# ReuseBlock_OPA847_2025-08-02.net
KiCad netlist of a schematic drawn in EasyEDA Pro
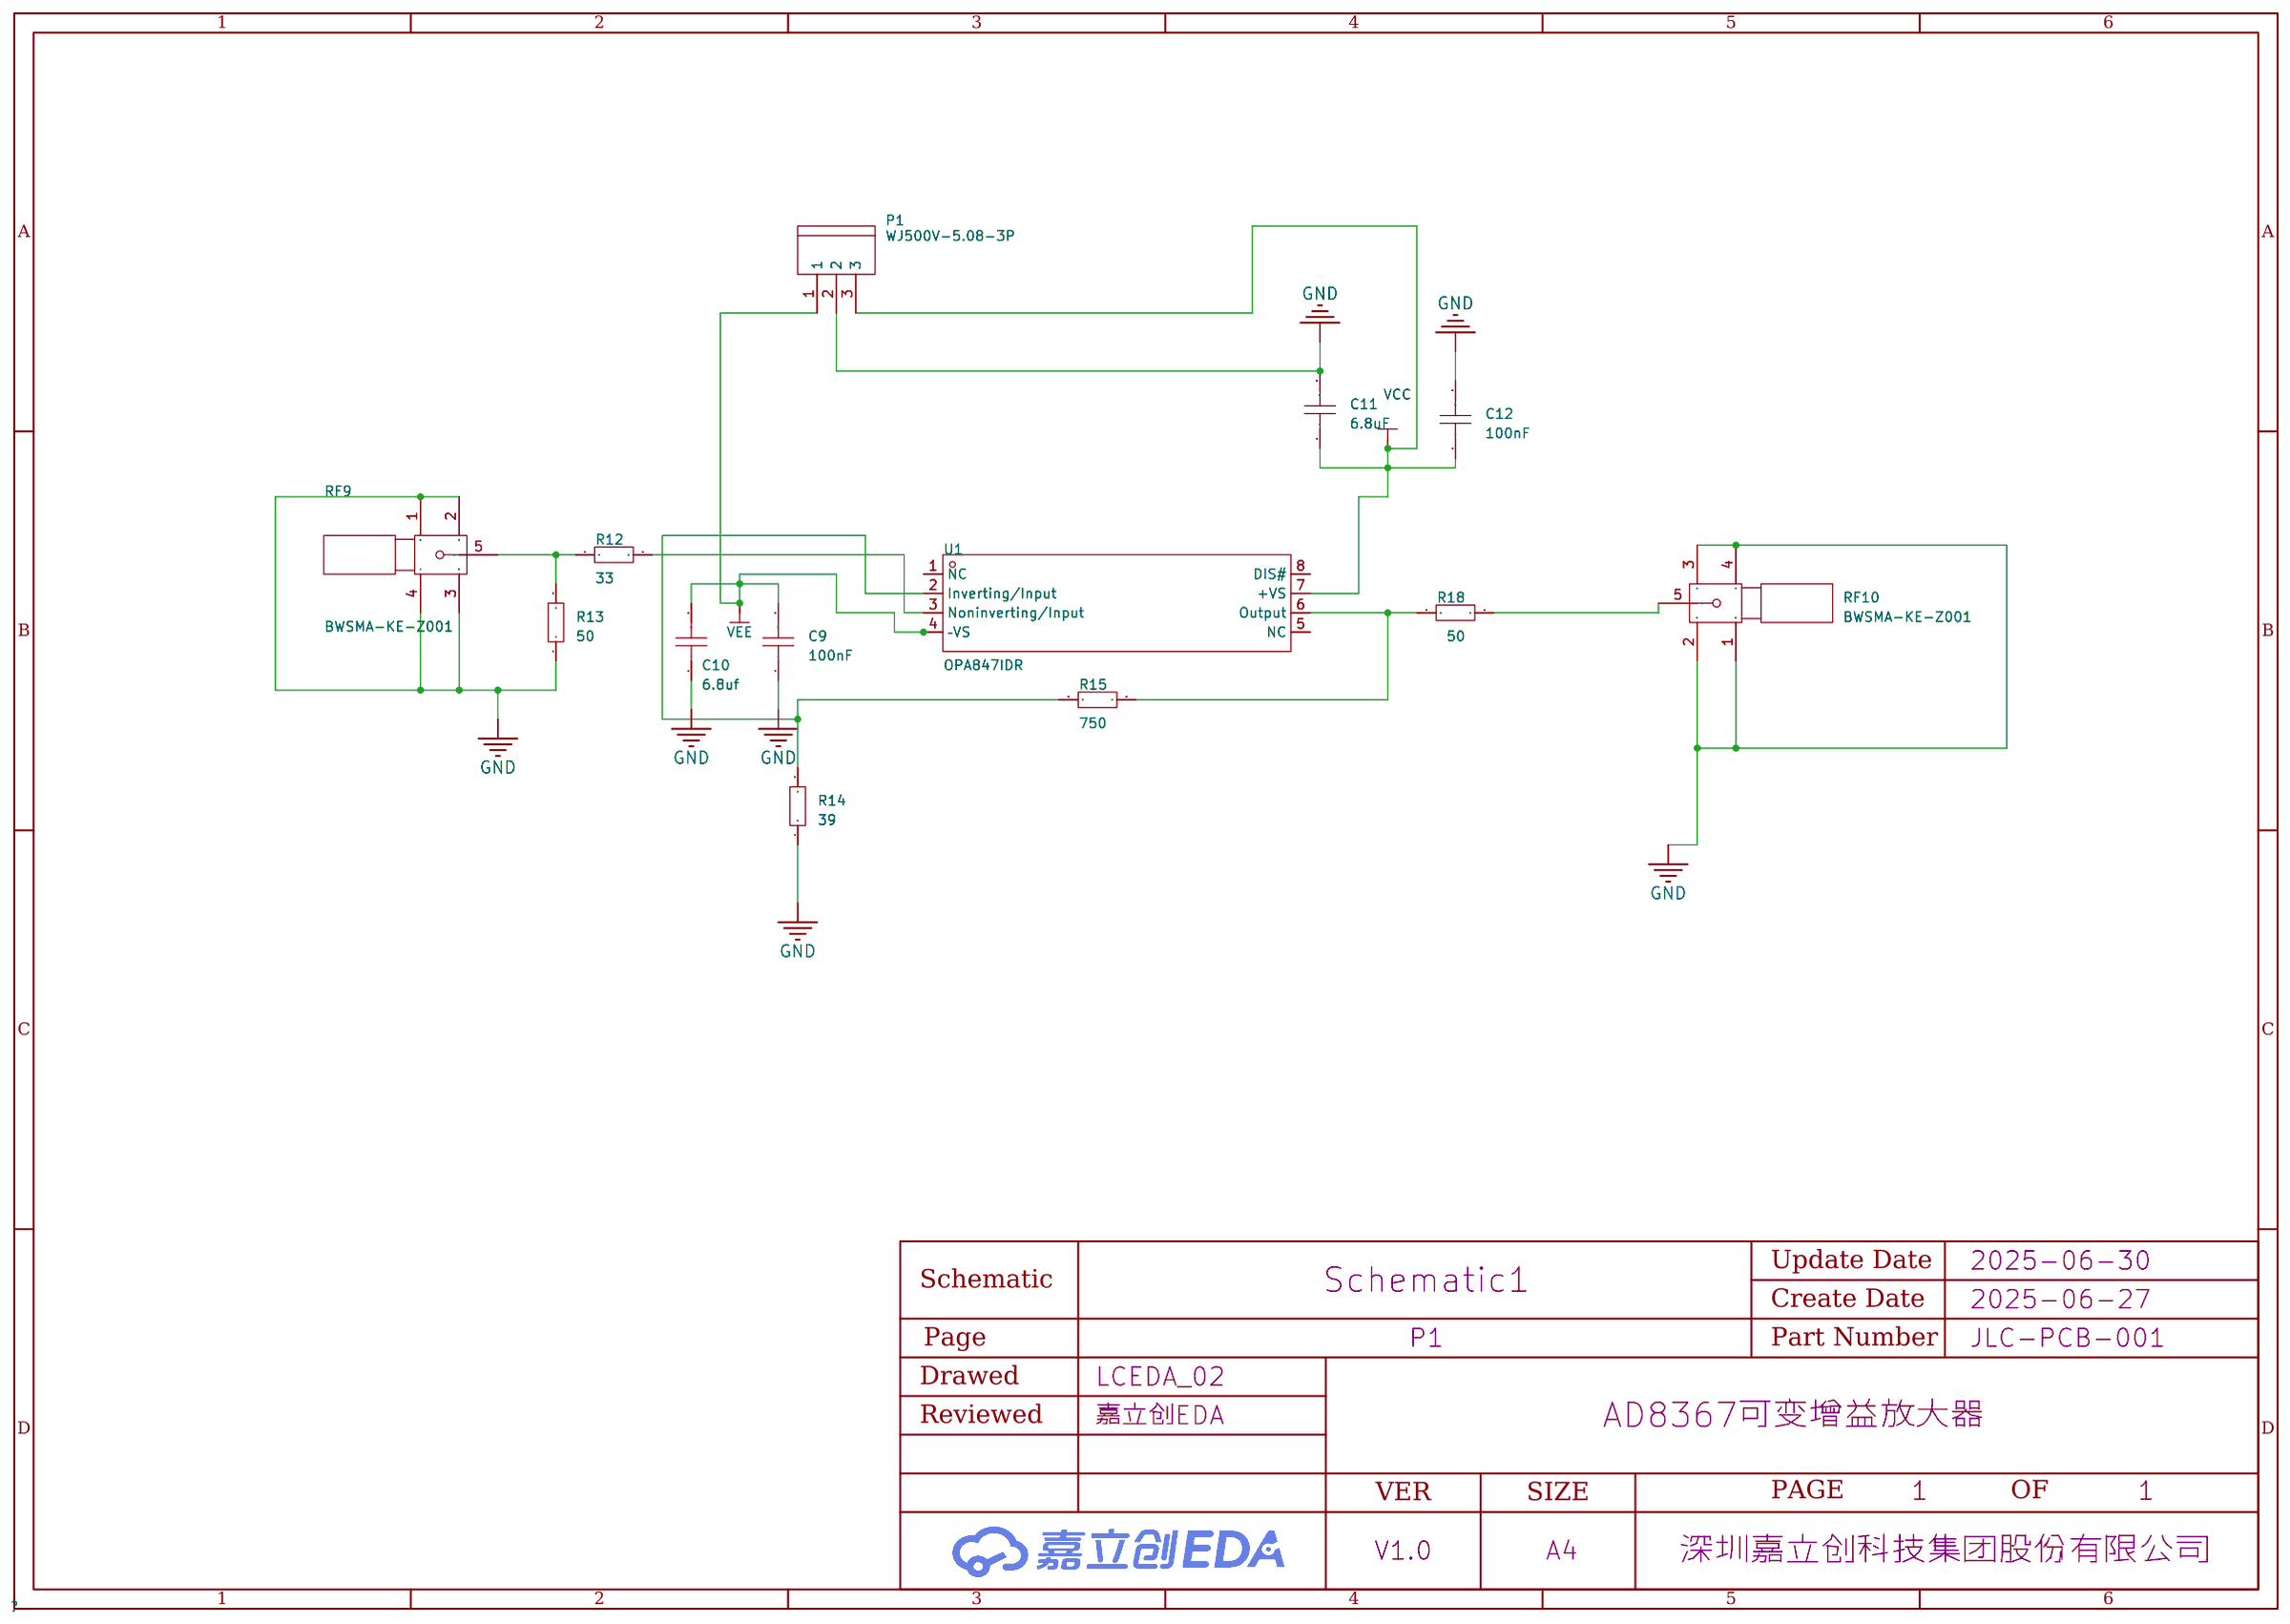
[diagram p0: schematic sheet]

(export (version "E")
  (design (tool "Eeschema 10.0.6"))
  (components
    (comp (ref "C9")
      (value "100nF")
      (footprint "easyedapro:C0805")
      (libsource (lib "easyedapro") (part "CapAcitance"))
    )
    (comp (ref "C10")
      (value "6.8uf")
      (footprint "easyedapro:C0805")
      (libsource (lib "easyedapro") (part "CapAcitance"))
    )
    (comp (ref "C11")
      (value "6.8uF")
      (footprint "easyedapro:C0805")
      (libsource (lib "easyedapro") (part "CapAcitance"))
    )
    (comp (ref "C12")
      (value "100nF")
      (footprint "easyedapro:C0805")
      (libsource (lib "easyedapro") (part "CapAcitance"))
    )
    (comp (ref "P1")
      (value "WJ500V-5.08-3P")
      (footprint "easyedapro:CONN-TH_3P-P5.00_WJ500V-5.08-3P")
      (fields (field (name "Manufacturer") "KANGNEX(康奈克斯电气)"))
      (libsource (lib "easyedapro") (part "WJ500V-5.08-3P-14-00A"))
    )
    (comp (ref "R12") (value "33") (footprint "easyedapro:R0805") (libsource (lib "easyedapro") (part "电阻")))
    (comp (ref "R13") (value "50") (footprint "easyedapro:R0805") (libsource (lib "easyedapro") (part "电阻")))
    (comp (ref "R14") (value "39") (footprint "easyedapro:R0805") (libsource (lib "easyedapro") (part "电阻")))
    (comp (ref "R15") (value "750") (footprint "easyedapro:R0805") (libsource (lib "easyedapro") (part "电阻")))
    (comp (ref "R18") (value "50") (footprint "easyedapro:R0805") (libsource (lib "easyedapro") (part "电阻")))
    (comp (ref "RF9")
      (value "BWSMA-KE-Z001")
      (footprint "easyedapro:SMA-TH_BWSMA-KE-Z001")
      (fields (field (name "Manufacturer") "BAT WIRELESS(蝙蝠无线)"))
      (libsource (lib "easyedapro") (part "BWSMA-KE-Z001"))
    )
    (comp (ref "RF10")
      (value "BWSMA-KE-Z001")
      (footprint "easyedapro:SMA-TH_BWSMA-KE-Z001")
      (fields (field (name "Manufacturer") "BAT WIRELESS(蝙蝠无线)"))
      (libsource (lib "easyedapro") (part "BWSMA-KE-Z001"))
    )
    (comp (ref "U1")
      (value "OPA847IDR")
      (footprint "easyedapro:SOIC-8_L4.9-W3.9-P1.27-LS6.0-TL")
      (description "放大器数:单路;增益带宽积(GBP):3.9GHz;压摆率(SR):950V/us;输入偏置电流(Ib):19uA;")
      (fields (field (name "Manufacturer") "TI(德州仪器)"))
      (libsource (lib "easyedapro") (part "OPA847IDR"))
    )
  )
  (nets
    (net (code "1") (name "GND") (class "Default")
      (node (ref "C10") (pin "1") (pinfunction "1_1") (pintype "input"))
      (node (ref "C11") (pin "2") (pinfunction "2_2") (pintype "input"))
      (node (ref "C12") (pin "2") (pinfunction "2_2") (pintype "input"))
      (node (ref "C9") (pin "1") (pinfunction "1_1") (pintype "input"))
      (node (ref "P1") (pin "2") (pinfunction "2_2") (pintype "unspecified"))
      (node (ref "R13") (pin "1") (pinfunction "1_1") (pintype "input"))
      (node (ref "R14") (pin "1") (pinfunction "1_1") (pintype "input"))
      (node (ref "RF10") (pin "1") (pinfunction "1_1") (pintype "unspecified"))
      (node (ref "RF10") (pin "2") (pinfunction "2_2") (pintype "unspecified"))
      (node (ref "RF10") (pin "3") (pinfunction "3_3") (pintype "unspecified"))
      (node (ref "RF10") (pin "4") (pinfunction "4_4") (pintype "unspecified"))
      (node (ref "RF9") (pin "1") (pinfunction "1_1") (pintype "unspecified"))
      (node (ref "RF9") (pin "2") (pinfunction "2_2") (pintype "unspecified"))
      (node (ref "RF9") (pin "3") (pinfunction "3_3") (pintype "unspecified"))
      (node (ref "RF9") (pin "4") (pinfunction "4_4") (pintype "unspecified"))
    )
    (net (code "2") (name "Net-(R12-Pad1)") (class "Default")
      (node (ref "R12") (pin "1") (pinfunction "1_1") (pintype "input"))
      (node (ref "R13") (pin "2") (pinfunction "2_2") (pintype "input"))
      (node (ref "RF9") (pin "5") (pinfunction "5_5") (pintype "unspecified"))
    )
    (net (code "3") (name "Net-(R18-Pad2)") (class "Default")
      (node (ref "R18") (pin "2") (pinfunction "2_2") (pintype "input"))
      (node (ref "RF10") (pin "5") (pinfunction "5_5") (pintype "unspecified"))
    )
    (net (code "4") (name "Net-(U1-Inverting{slash}Input)") (class "Default")
      (node (ref "R14") (pin "2") (pinfunction "2_2") (pintype "input"))
      (node (ref "R15") (pin "1") (pinfunction "1_1") (pintype "input"))
      (node (ref "U1") (pin "2") (pinfunction "Inverting/Input_2") (pintype "unspecified"))
    )
    (net (code "5") (name "Net-(U1-Noninverting{slash}Input)") (class "Default")
      (node (ref "R12") (pin "2") (pinfunction "2_2") (pintype "input"))
      (node (ref "U1") (pin "3") (pinfunction "Noninverting/Input_3") (pintype "unspecified"))
    )
    (net (code "6") (name "Net-(U1-Output)") (class "Default")
      (node (ref "R15") (pin "2") (pinfunction "2_2") (pintype "input"))
      (node (ref "R18") (pin "1") (pinfunction "1_1") (pintype "input"))
      (node (ref "U1") (pin "6") (pinfunction "Output_6") (pintype "unspecified"))
    )
    (net (code "7") (name "VCC") (class "Default")
      (node (ref "C11") (pin "1") (pinfunction "1_1") (pintype "input"))
      (node (ref "C12") (pin "1") (pinfunction "1_1") (pintype "input"))
      (node (ref "P1") (pin "3") (pinfunction "3_3") (pintype "unspecified"))
      (node (ref "U1") (pin "7") (pinfunction "+VS_7") (pintype "unspecified"))
    )
    (net (code "8") (name "VEE") (class "Default")
      (node (ref "C10") (pin "2") (pinfunction "2_2") (pintype "input"))
      (node (ref "C9") (pin "2") (pinfunction "2_2") (pintype "input"))
      (node (ref "P1") (pin "1") (pinfunction "1_1") (pintype "unspecified"))
      (node (ref "U1") (pin "4") (pinfunction "–VS_4") (pintype "unspecified"))
    )
    (net (code "9") (name "unconnected-(U1-DIS#-Pad8)") (class "Default")
      (node (ref "U1") (pin "8") (pinfunction "DIS#_8") (pintype "unspecified"))
    )
    (net (code "10") (name "unconnected-(U1-NC-Pad1)") (class "Default")
      (node (ref "U1") (pin "1") (pinfunction "NC_1") (pintype "unspecified"))
    )
    (net (code "11") (name "unconnected-(U1-NC-Pad5)") (class "Default")
      (node (ref "U1") (pin "5") (pinfunction "NC_5") (pintype "unspecified"))
    )
  )
)
